# GPS_radiologger_v24_L70_CMWX_MAX_v12.net
KiCad netlist of a schematic drawn in EAGLE
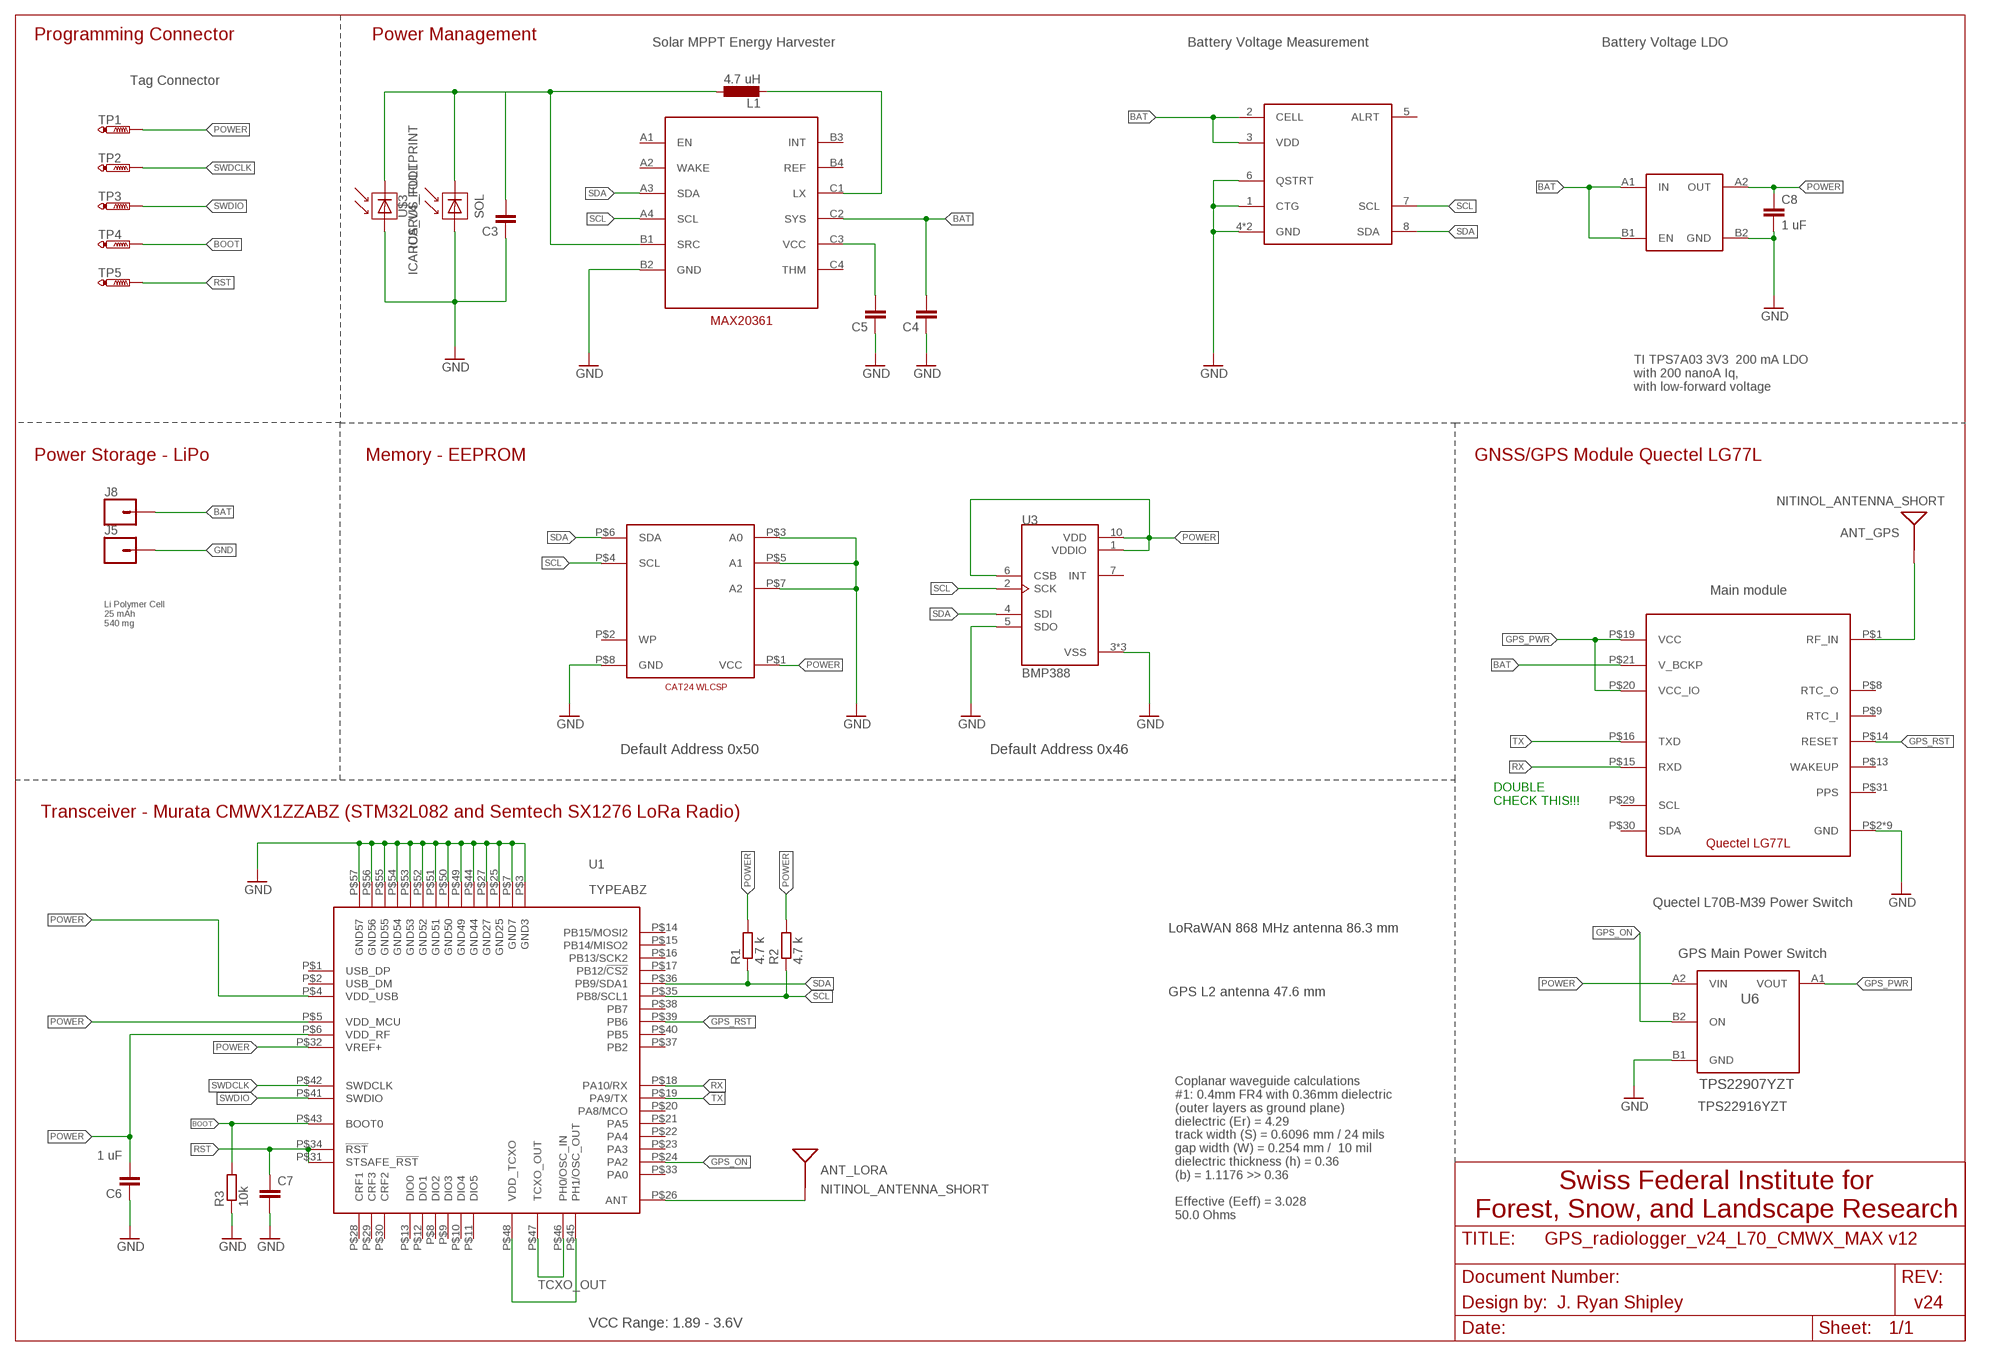
[diagram p0: schematic, sheet 1]

(export (version "E")
  (design (tool "Eeschema 10.0.6"))
  (components
    (comp (ref "ANT_GPS")
      (value "NITINOL_ANTENNA_SHORT")
      (footprint "eagle-import:ICARUS_NITINOL_ANTENNA_SHORT")
      (libsource (lib "eagle-import") (part "NITINOL_ANTENNA_SHORT"))
    )
    (comp (ref "ANT_LORA")
      (value "NITINOL_ANTENNA_SHORT")
      (footprint "eagle-import:ICARUS_NITINOL_ANTENNA_SHORT")
      (libsource (lib "eagle-import") (part "NITINOL_ANTENNA_SHORT"))
    )
    (comp (ref "C3")
      (value "10UF")
      (footprint "eagle-import:0603-TIGHT")
      (libsource (lib "eagle-import") (part "10UF"))
    )
    (comp (ref "C4")
      (value "1.0UF")
      (footprint "eagle-import:0402-TIGHTER")
      (libsource (lib "eagle-import") (part "1.0UF"))
    )
    (comp (ref "C5")
      (value "1.0UF")
      (footprint "eagle-import:0402-TIGHTER")
      (libsource (lib "eagle-import") (part "1.0UF"))
    )
    (comp (ref "C6")
      (value "1 uF")
      (footprint "eagle-import:0402-TIGHTER")
      (libsource (lib "eagle-import") (part "1.0UF"))
    )
    (comp (ref "C7")
      (value "C-EUC0201")
      (footprint "eagle-import:C0201")
      (libsource (lib "eagle-import") (part "C-EUC0201"))
    )
    (comp (ref "C8")
      (value "1 uF")
      (footprint "eagle-import:0402-TIGHTER")
      (libsource (lib "eagle-import") (part "1.0UF"))
    )
    (comp (ref "J5")
      (value "CONN_01PTH_NO_SILK_SMALL")
      (footprint "eagle-import:1X01_SMALL")
      (libsource (lib "eagle-import") (part "CONN_01PTH_NO_SILK_SMALL"))
    )
    (comp (ref "J8")
      (value "CONN_01PTH_NO_SILK_SMALL")
      (footprint "eagle-import:1X01_SMALL")
      (libsource (lib "eagle-import") (part "CONN_01PTH_NO_SILK_SMALL"))
    )
    (comp (ref "L1")
      (value "4.7 uH")
      (footprint "eagle-import:INDC2016X120L")
      (libsource (lib "eagle-import") (part "IND_2016"))
    )
    (comp (ref "R1")
      (value "4.7 k")
      (footprint "eagle-import:R0201")
      (libsource (lib "eagle-import") (part "R-EU_R0201"))
    )
    (comp (ref "R2")
      (value "4.7 k")
      (footprint "eagle-import:R0201")
      (libsource (lib "eagle-import") (part "R-EU_R0201"))
    )
    (comp (ref "R3")
      (value "10k")
      (footprint "eagle-import:R0201")
      (libsource (lib "eagle-import") (part "R-EU_R0201"))
    )
    (comp (ref "SOL")
      (value "ICARUS_V4_FOOTPRINT")
      (footprint "eagle-import:ICARUS_FULL_FOOTPRINT")
      (libsource (lib "eagle-import") (part "ICARUS_V4_FOOTPRINT"))
    )
    (comp (ref "TP1")
      (value "PTR1TP08SQ")
      (footprint "eagle-import:TP08SQ")
      (libsource (lib "eagle-import") (part "PTR1TP08SQ"))
    )
    (comp (ref "TP2")
      (value "PTR1TP08SQ")
      (footprint "eagle-import:TP08SQ")
      (libsource (lib "eagle-import") (part "PTR1TP08SQ"))
    )
    (comp (ref "TP3")
      (value "PTR1TP08SQ")
      (footprint "eagle-import:TP08SQ")
      (libsource (lib "eagle-import") (part "PTR1TP08SQ"))
    )
    (comp (ref "TP4")
      (value "PTR1TP08SQ")
      (footprint "eagle-import:TP08SQ")
      (libsource (lib "eagle-import") (part "PTR1TP08SQ"))
    )
    (comp (ref "TP5")
      (value "PTR1TP08SQ")
      (footprint "eagle-import:TP08SQ")
      (libsource (lib "eagle-import") (part "PTR1TP08SQ"))
    )
    (comp (ref "U$3")
      (value "ICARUS_FULL")
      (footprint "eagle-import:ICARUS_FULL")
      (libsource (lib "eagle-import") (part "ICARUS_FULL"))
    )
    (comp (ref "U1")
      (value "TYPEABZ")
      (footprint "eagle-import:TYPEABZ")
      (libsource (lib "eagle-import") (part "TYPEABZ"))
    )
    (comp (ref "U2")
      (value "LG77L")
      (footprint "eagle-import:LG77L")
      (libsource (lib "eagle-import") (part "LG77L"))
    )
    (comp (ref "U3")
      (value "BMP388")
      (footprint "eagle-import:PQFN50P200X200X80-10N")
      (fields (field (name "MF") "Bosch Sensortec"))
      (libsource (lib "eagle-import") (part "BMP388"))
    )
    (comp (ref "U4")
      (value "TPS7A03-DSBGA")
      (footprint "eagle-import:BGA4N35P2X2_70X70X40N")
      (libsource (lib "eagle-import") (part "TPS7A03-DSBGA"))
    )
    (comp (ref "U5")
      (value "MAX17048G+")
      (footprint "eagle-import:SON50P200X200X75-9T80X120L")
      (libsource (lib "eagle-import") (part "MAX17048G+"))
    )
    (comp (ref "U6")
      (value "TPS22907YZT")
      (footprint "eagle-import:YFP0004-DSBGA")
      (libsource (lib "eagle-import") (part "TPS22907YZT"))
    )
    (comp (ref "U7")
      (value "CAT24_WLCSP8")
      (footprint "eagle-import:WLCSP8")
      (libsource (lib "eagle-import") (part "CAT24_WLCSP8"))
    )
    (comp (ref "U8")
      (value "MAX20361")
      (footprint "eagle-import:BGA12N40P4X3_123X163X64N")
      (libsource (lib "eagle-import") (part "MAX20361"))
    )
  )
  (nets
    (net (code "1") (name "/TCXO_OUT") (class "Default")
      (node (ref "U1") (pin "P$46") (pinfunction "PH0/OSC_IN_P$46") (pintype "bidirectional"))
      (node (ref "U1") (pin "P$47") (pinfunction "TCXO_OUT_P$47") (pintype "bidirectional"))
    )
    (net (code "2") (name "BAT") (class "Default")
      (node (ref "C4") (pin "P$2") (pinfunction "2_P$2") (pintype "passive"))
      (node (ref "J8") (pin "P$1") (pinfunction "1_P$1") (pintype "passive"))
      (node (ref "U2") (pin "P$21") (pinfunction "V_BCKP_P$21") (pintype "bidirectional"))
      (node (ref "U4") (pin "A1") (pinfunction "IN_A1") (pintype "bidirectional"))
      (node (ref "U4") (pin "B1") (pinfunction "EN_B1") (pintype "bidirectional"))
      (node (ref "U5") (pin "2") (pinfunction "CELL_2") (pintype "bidirectional"))
      (node (ref "U5") (pin "3") (pinfunction "VDD_3") (pintype "bidirectional"))
      (node (ref "U8") (pin "C2") (pinfunction "SYS_C2") (pintype "bidirectional"))
    )
    (net (code "3") (name "BOOT") (class "Default")
      (node (ref "R3") (pin "2") (pinfunction "2_2") (pintype "passive"))
      (node (ref "TP4") (pin "TP") (pinfunction "TP_TP") (pintype "input"))
      (node (ref "U1") (pin "P$43") (pinfunction "BOOT0_P$43") (pintype "bidirectional"))
    )
    (net (code "4") (name "GND") (class "Default")
      (node (ref "C3") (pin "P$1") (pinfunction "1_P$1") (pintype "passive"))
      (node (ref "C4") (pin "P$1") (pinfunction "1_P$1") (pintype "passive"))
      (node (ref "C5") (pin "P$1") (pinfunction "1_P$1") (pintype "passive"))
      (node (ref "C6") (pin "P$1") (pinfunction "1_P$1") (pintype "passive"))
      (node (ref "C7") (pin "2") (pinfunction "2_2") (pintype "passive"))
      (node (ref "C8") (pin "P$2") (pinfunction "2_P$2") (pintype "passive"))
      (node (ref "J5") (pin "P$1") (pinfunction "1_P$1") (pintype "passive"))
      (node (ref "R3") (pin "1") (pinfunction "1_1") (pintype "passive"))
      (node (ref "SOL") (pin "P$2") (pinfunction "MINUS_P$2") (pintype "passive"))
      (node (ref "U$3") (pin "P$2") (pinfunction "MINUS_P$2") (pintype "passive"))
      (node (ref "U1") (pin "P$25") (pinfunction "GND25_P$25") (pintype "power_in"))
      (node (ref "U1") (pin "P$27") (pinfunction "GND27_P$27") (pintype "power_in"))
      (node (ref "U1") (pin "P$3") (pinfunction "GND3_P$3") (pintype "power_in"))
      (node (ref "U1") (pin "P$44") (pinfunction "GND44_P$44") (pintype "power_in"))
      (node (ref "U1") (pin "P$49") (pinfunction "GND49_P$49") (pintype "power_in"))
      (node (ref "U1") (pin "P$50") (pinfunction "GND50_P$50") (pintype "power_in"))
      (node (ref "U1") (pin "P$51") (pinfunction "GND51_P$51") (pintype "power_in"))
      (node (ref "U1") (pin "P$52") (pinfunction "GND52_P$52") (pintype "power_in"))
      (node (ref "U1") (pin "P$53") (pinfunction "GND53_P$53") (pintype "power_in"))
      (node (ref "U1") (pin "P$54") (pinfunction "GND54_P$54") (pintype "power_in"))
      (node (ref "U1") (pin "P$55") (pinfunction "GND55_P$55") (pintype "power_in"))
      (node (ref "U1") (pin "P$56") (pinfunction "GND56_P$56") (pintype "power_in"))
      (node (ref "U1") (pin "P$57") (pinfunction "GND57_P$57") (pintype "power_in"))
      (node (ref "U1") (pin "P$7") (pinfunction "GND7_P$7") (pintype "power_in"))
      (node (ref "U2") (pin "P$18") (pinfunction "GND_P$18") (pintype "bidirectional"))
      (node (ref "U2") (pin "P$2") (pinfunction "GND_P$2") (pintype "bidirectional"))
      (node (ref "U2") (pin "P$37") (pinfunction "GND_P$37") (pintype "bidirectional"))
      (node (ref "U2") (pin "P$38") (pinfunction "GND_P$38") (pintype "bidirectional"))
      (node (ref "U2") (pin "P$39") (pinfunction "GND_P$39") (pintype "bidirectional"))
      (node (ref "U2") (pin "P$40") (pinfunction "GND_P$40") (pintype "bidirectional"))
      (node (ref "U2") (pin "P$41") (pinfunction "GND_P$41") (pintype "bidirectional"))
      (node (ref "U2") (pin "P$42") (pinfunction "GND_P$42") (pintype "bidirectional"))
      (node (ref "U2") (pin "P$43") (pinfunction "GND_P$43") (pintype "bidirectional"))
      (node (ref "U3") (pin "3") (pinfunction "VSS_3") (pintype "power_in"))
      (node (ref "U3") (pin "5") (pinfunction "SDO_5") (pintype "bidirectional"))
      (node (ref "U3") (pin "8") (pinfunction "VSS_8") (pintype "power_in"))
      (node (ref "U3") (pin "9") (pinfunction "VSS_9") (pintype "power_in"))
      (node (ref "U4") (pin "B2") (pinfunction "GND_B2") (pintype "bidirectional"))
      (node (ref "U5") (pin "1") (pinfunction "CTG_1") (pintype "bidirectional"))
      (node (ref "U5") (pin "4") (pinfunction "GND_4") (pintype "bidirectional"))
      (node (ref "U5") (pin "6") (pinfunction "QSTRT_6") (pintype "bidirectional"))
      (node (ref "U5") (pin "9") (pinfunction "GND_9") (pintype "bidirectional"))
      (node (ref "U6") (pin "B1") (pinfunction "GND_B1") (pintype "bidirectional"))
      (node (ref "U7") (pin "P$3") (pinfunction "A0_P$3") (pintype "bidirectional"))
      (node (ref "U7") (pin "P$5") (pinfunction "A1_P$5") (pintype "bidirectional"))
      (node (ref "U7") (pin "P$7") (pinfunction "A2_P$7") (pintype "bidirectional"))
      (node (ref "U7") (pin "P$8") (pinfunction "GND_P$8") (pintype "bidirectional"))
      (node (ref "U8") (pin "B2") (pinfunction "GND_B2") (pintype "bidirectional"))
    )
    (net (code "5") (name "GPS_ON") (class "Default")
      (node (ref "U1") (pin "P$24") (pinfunction "PA2_P$24") (pintype "bidirectional"))
      (node (ref "U6") (pin "B2") (pinfunction "ON_B2") (pintype "bidirectional"))
    )
    (net (code "6") (name "GPS_PWR") (class "Default")
      (node (ref "U2") (pin "P$19") (pinfunction "VCC_P$19") (pintype "bidirectional"))
      (node (ref "U2") (pin "P$20") (pinfunction "VCC_IO_P$20") (pintype "bidirectional"))
      (node (ref "U6") (pin "A1") (pinfunction "VOUT_A1") (pintype "bidirectional"))
    )
    (net (code "7") (name "GPS_RST") (class "Default")
      (node (ref "U1") (pin "P$39") (pinfunction "PB6_P$39") (pintype "bidirectional"))
      (node (ref "U2") (pin "P$14") (pinfunction "RESET_P$14") (pintype "bidirectional"))
    )
    (net (code "8") (name "Net-(C3-2)") (class "Default")
      (node (ref "C3") (pin "P$2") (pinfunction "2_P$2") (pintype "passive"))
      (node (ref "L1") (pin "1") (pinfunction "1_1") (pintype "passive"))
      (node (ref "SOL") (pin "P$1") (pinfunction "PLUS_P$1") (pintype "passive"))
      (node (ref "U$3") (pin "P$1") (pinfunction "PLUS_P$1") (pintype "passive"))
      (node (ref "U8") (pin "B1") (pinfunction "SRC_B1") (pintype "bidirectional"))
    )
    (net (code "9") (name "Net-(C5-2)") (class "Default")
      (node (ref "C5") (pin "P$2") (pinfunction "2_P$2") (pintype "passive"))
      (node (ref "U8") (pin "C3") (pinfunction "VCC_C3") (pintype "bidirectional"))
    )
    (net (code "10") (name "Net-(U1-ANT)") (class "Default")
      (node (ref "ANT_LORA") (pin "1") (pinfunction "SIGNAL_1") (pintype "bidirectional"))
      (node (ref "ANT_LORA") (pin "2") (pinfunction "SIGNAL_2") (pintype "bidirectional"))
      (node (ref "ANT_LORA") (pin "3") (pinfunction "SIGNAL_3") (pintype "bidirectional"))
      (node (ref "U1") (pin "P$26") (pinfunction "ANT_P$26") (pintype "bidirectional"))
    )
    (net (code "11") (name "Net-(U1-PH1{slash}OSC_OUT)") (class "Default")
      (node (ref "U1") (pin "P$45") (pinfunction "PH1/OSC_OUT_P$45") (pintype "bidirectional"))
      (node (ref "U1") (pin "P$48") (pinfunction "VDD_TCXO_P$48") (pintype "power_in"))
    )
    (net (code "12") (name "Net-(U2-RF_IN)") (class "Default")
      (node (ref "ANT_GPS") (pin "1") (pinfunction "SIGNAL_1") (pintype "bidirectional"))
      (node (ref "ANT_GPS") (pin "2") (pinfunction "SIGNAL_2") (pintype "bidirectional"))
      (node (ref "ANT_GPS") (pin "3") (pinfunction "SIGNAL_3") (pintype "bidirectional"))
      (node (ref "U2") (pin "P$1") (pinfunction "RF_IN_P$1") (pintype "bidirectional"))
    )
    (net (code "13") (name "Net-(U8-LX)") (class "Default")
      (node (ref "L1") (pin "2") (pinfunction "2_2") (pintype "passive"))
      (node (ref "U8") (pin "C1") (pinfunction "LX_C1") (pintype "bidirectional"))
    )
    (net (code "14") (name "POWER") (class "Default")
      (node (ref "C6") (pin "P$2") (pinfunction "2_P$2") (pintype "passive"))
      (node (ref "C8") (pin "P$1") (pinfunction "1_P$1") (pintype "passive"))
      (node (ref "R1") (pin "2") (pinfunction "2_2") (pintype "passive"))
      (node (ref "R2") (pin "2") (pinfunction "2_2") (pintype "passive"))
      (node (ref "TP1") (pin "TP") (pinfunction "TP_TP") (pintype "input"))
      (node (ref "U1") (pin "P$32") (pinfunction "VREF+_P$32") (pintype "power_in"))
      (node (ref "U1") (pin "P$4") (pinfunction "VDD_USB_P$4") (pintype "power_in"))
      (node (ref "U1") (pin "P$5") (pinfunction "VDD_MCU_P$5") (pintype "power_in"))
      (node (ref "U1") (pin "P$6") (pinfunction "VDD_RF_P$6") (pintype "power_in"))
      (node (ref "U3") (pin "1") (pinfunction "VDDIO_1") (pintype "power_in"))
      (node (ref "U3") (pin "10") (pinfunction "VDD_10") (pintype "power_in"))
      (node (ref "U3") (pin "6") (pinfunction "CSB_6") (pintype "input"))
      (node (ref "U4") (pin "A2") (pinfunction "OUT_A2") (pintype "bidirectional"))
      (node (ref "U6") (pin "A2") (pinfunction "VIN_A2") (pintype "bidirectional"))
      (node (ref "U7") (pin "P$1") (pinfunction "VCC_P$1") (pintype "bidirectional"))
    )
    (net (code "15") (name "RST") (class "Default")
      (node (ref "C7") (pin "1") (pinfunction "1_1") (pintype "passive"))
      (node (ref "TP5") (pin "TP") (pinfunction "TP_TP") (pintype "input"))
      (node (ref "U1") (pin "P$31") (pinfunction "STSAFE_~{RST}_P$31") (pintype "bidirectional"))
      (node (ref "U1") (pin "P$34") (pinfunction "~{RST}_P$34") (pintype "bidirectional"))
    )
    (net (code "16") (name "RX") (class "Default")
      (node (ref "U1") (pin "P$18") (pinfunction "PA10/RX_P$18") (pintype "bidirectional"))
      (node (ref "U2") (pin "P$15") (pinfunction "RXD_P$15") (pintype "bidirectional"))
    )
    (net (code "17") (name "SCL") (class "Default")
      (node (ref "R2") (pin "1") (pinfunction "1_1") (pintype "passive"))
      (node (ref "U1") (pin "P$35") (pinfunction "PB8/SCL1_P$35") (pintype "bidirectional"))
      (node (ref "U3") (pin "2") (pinfunction "SCK_2") (pintype "input"))
      (node (ref "U5") (pin "7") (pinfunction "SCL_7") (pintype "bidirectional"))
      (node (ref "U7") (pin "P$4") (pinfunction "SCL_P$4") (pintype "bidirectional"))
      (node (ref "U8") (pin "A4") (pinfunction "SCL_A4") (pintype "bidirectional"))
    )
    (net (code "18") (name "SDA") (class "Default")
      (node (ref "R1") (pin "1") (pinfunction "1_1") (pintype "passive"))
      (node (ref "U1") (pin "P$36") (pinfunction "PB9/SDA1_P$36") (pintype "bidirectional"))
      (node (ref "U3") (pin "4") (pinfunction "SDI_4") (pintype "bidirectional"))
      (node (ref "U5") (pin "8") (pinfunction "SDA_8") (pintype "bidirectional"))
      (node (ref "U7") (pin "P$6") (pinfunction "SDA_P$6") (pintype "bidirectional"))
      (node (ref "U8") (pin "A3") (pinfunction "SDA_A3") (pintype "bidirectional"))
    )
    (net (code "19") (name "SWDCLK") (class "Default")
      (node (ref "TP2") (pin "TP") (pinfunction "TP_TP") (pintype "input"))
      (node (ref "U1") (pin "P$42") (pinfunction "SWDCLK_P$42") (pintype "bidirectional"))
    )
    (net (code "20") (name "SWDIO") (class "Default")
      (node (ref "TP3") (pin "TP") (pinfunction "TP_TP") (pintype "input"))
      (node (ref "U1") (pin "P$41") (pinfunction "SWDIO_P$41") (pintype "bidirectional"))
    )
    (net (code "21") (name "TX") (class "Default")
      (node (ref "U1") (pin "P$19") (pinfunction "PA9/TX_P$19") (pintype "bidirectional"))
      (node (ref "U2") (pin "P$16") (pinfunction "TXD_P$16") (pintype "bidirectional"))
    )
    (net (code "22") (name "unconnected-(U1-CRF1-PadP$28)") (class "Default")
      (node (ref "U1") (pin "P$28") (pinfunction "CRF1_P$28") (pintype "no_connect"))
    )
    (net (code "23") (name "unconnected-(U1-CRF2-PadP$30)") (class "Default")
      (node (ref "U1") (pin "P$30") (pinfunction "CRF2_P$30") (pintype "no_connect"))
    )
    (net (code "24") (name "unconnected-(U1-CRF3-PadP$29)") (class "Default")
      (node (ref "U1") (pin "P$29") (pinfunction "CRF3_P$29") (pintype "no_connect"))
    )
    (net (code "25") (name "unconnected-(U1-DIO0-PadP$13)") (class "Default")
      (node (ref "U1") (pin "P$13") (pinfunction "DIO0_P$13") (pintype "no_connect"))
    )
    (net (code "26") (name "unconnected-(U1-DIO1-PadP$12)") (class "Default")
      (node (ref "U1") (pin "P$12") (pinfunction "DIO1_P$12") (pintype "no_connect"))
    )
    (net (code "27") (name "unconnected-(U1-DIO2-PadP$8)") (class "Default")
      (node (ref "U1") (pin "P$8") (pinfunction "DIO2_P$8") (pintype "no_connect"))
    )
    (net (code "28") (name "unconnected-(U1-DIO3-PadP$9)") (class "Default")
      (node (ref "U1") (pin "P$9") (pinfunction "DIO3_P$9") (pintype "no_connect"))
    )
    (net (code "29") (name "unconnected-(U1-DIO4-PadP$10)") (class "Default")
      (node (ref "U1") (pin "P$10") (pinfunction "DIO4_P$10") (pintype "bidirectional"))
    )
    (net (code "30") (name "unconnected-(U1-DIO5-PadP$11)") (class "Default")
      (node (ref "U1") (pin "P$11") (pinfunction "DIO5_P$11") (pintype "bidirectional"))
    )
    (net (code "31") (name "unconnected-(U1-PA0-PadP$33)") (class "Default")
      (node (ref "U1") (pin "P$33") (pinfunction "PA0_P$33") (pintype "bidirectional"))
    )
    (net (code "32") (name "unconnected-(U1-PA3-PadP$23)") (class "Default")
      (node (ref "U1") (pin "P$23") (pinfunction "PA3_P$23") (pintype "bidirectional"))
    )
    (net (code "33") (name "unconnected-(U1-PA4-PadP$22)") (class "Default")
      (node (ref "U1") (pin "P$22") (pinfunction "PA4_P$22") (pintype "bidirectional"))
    )
    (net (code "34") (name "unconnected-(U1-PA5-PadP$21)") (class "Default")
      (node (ref "U1") (pin "P$21") (pinfunction "PA5_P$21") (pintype "bidirectional"))
    )
    (net (code "35") (name "unconnected-(U1-PA8{slash}MCO-PadP$20)") (class "Default")
      (node (ref "U1") (pin "P$20") (pinfunction "PA8/MCO_P$20") (pintype "bidirectional"))
    )
    (net (code "36") (name "unconnected-(U1-PB2-PadP$37)") (class "Default")
      (node (ref "U1") (pin "P$37") (pinfunction "PB2_P$37") (pintype "bidirectional"))
    )
    (net (code "37") (name "unconnected-(U1-PB5-PadP$40)") (class "Default")
      (node (ref "U1") (pin "P$40") (pinfunction "PB5_P$40") (pintype "bidirectional"))
    )
    (net (code "38") (name "unconnected-(U1-PB7-PadP$38)") (class "Default")
      (node (ref "U1") (pin "P$38") (pinfunction "PB7_P$38") (pintype "bidirectional"))
    )
    (net (code "39") (name "unconnected-(U1-PB12{slash}~{CS2}-PadP$17)") (class "Default")
      (node (ref "U1") (pin "P$17") (pinfunction "PB12/~{CS2}_P$17") (pintype "bidirectional"))
    )
    (net (code "40") (name "unconnected-(U1-PB13{slash}SCK2-PadP$16)") (class "Default")
      (node (ref "U1") (pin "P$16") (pinfunction "PB13/SCK2_P$16") (pintype "bidirectional"))
    )
    (net (code "41") (name "unconnected-(U1-PB14{slash}MISO2-PadP$15)") (class "Default")
      (node (ref "U1") (pin "P$15") (pinfunction "PB14/MISO2_P$15") (pintype "bidirectional"))
    )
    (net (code "42") (name "unconnected-(U1-PB15{slash}MOSI2-PadP$14)") (class "Default")
      (node (ref "U1") (pin "P$14") (pinfunction "PB15/MOSI2_P$14") (pintype "bidirectional"))
    )
    (net (code "43") (name "unconnected-(U1-USB_DM-PadP$2)") (class "Default")
      (node (ref "U1") (pin "P$2") (pinfunction "USB_DM_P$2") (pintype "bidirectional"))
    )
    (net (code "44") (name "unconnected-(U1-USB_DP-PadP$1)") (class "Default")
      (node (ref "U1") (pin "P$1") (pinfunction "USB_DP_P$1") (pintype "bidirectional"))
    )
    (net (code "45") (name "unconnected-(U2-PPS-PadP$31)") (class "Default")
      (node (ref "U2") (pin "P$31") (pinfunction "PPS_P$31") (pintype "bidirectional"))
    )
    (net (code "46") (name "unconnected-(U2-RTC_I-PadP$9)") (class "Default")
      (node (ref "U2") (pin "P$9") (pinfunction "RTC_I_P$9") (pintype "bidirectional"))
    )
    (net (code "47") (name "unconnected-(U2-RTC_O-PadP$8)") (class "Default")
      (node (ref "U2") (pin "P$8") (pinfunction "RTC_O_P$8") (pintype "bidirectional"))
    )
    (net (code "48") (name "unconnected-(U2-SCL-PadP$29)") (class "Default")
      (node (ref "U2") (pin "P$29") (pinfunction "SCL_P$29") (pintype "bidirectional"))
    )
    (net (code "49") (name "unconnected-(U2-SDA-PadP$30)") (class "Default")
      (node (ref "U2") (pin "P$30") (pinfunction "SDA_P$30") (pintype "bidirectional"))
    )
    (net (code "50") (name "unconnected-(U2-WAKEUP-PadP$13)") (class "Default")
      (node (ref "U2") (pin "P$13") (pinfunction "WAKEUP_P$13") (pintype "bidirectional"))
    )
    (net (code "51") (name "unconnected-(U3-INT-Pad7)") (class "Default")
      (node (ref "U3") (pin "7") (pinfunction "INT_7") (pintype "output"))
    )
    (net (code "52") (name "unconnected-(U5-ALRT-Pad5)") (class "Default")
      (node (ref "U5") (pin "5") (pinfunction "ALRT_5") (pintype "bidirectional"))
    )
    (net (code "53") (name "unconnected-(U7-WP-PadP$2)") (class "Default")
      (node (ref "U7") (pin "P$2") (pinfunction "WP_P$2") (pintype "bidirectional"))
    )
    (net (code "54") (name "unconnected-(U8-EN-PadA1)") (class "Default")
      (node (ref "U8") (pin "A1") (pinfunction "EN_A1") (pintype "bidirectional"))
    )
    (net (code "55") (name "unconnected-(U8-INT-PadB3)") (class "Default")
      (node (ref "U8") (pin "B3") (pinfunction "INT_B3") (pintype "bidirectional"))
    )
    (net (code "56") (name "unconnected-(U8-REF-PadB4)") (class "Default")
      (node (ref "U8") (pin "B4") (pinfunction "REF_B4") (pintype "bidirectional"))
    )
    (net (code "57") (name "unconnected-(U8-THM-PadC4)") (class "Default")
      (node (ref "U8") (pin "C4") (pinfunction "THM_C4") (pintype "bidirectional"))
    )
    (net (code "58") (name "unconnected-(U8-WAKE-PadA2)") (class "Default")
      (node (ref "U8") (pin "A2") (pinfunction "WAKE_A2") (pintype "bidirectional"))
    )
  )
)
